# SCH_2023-10-16.net
KiCad netlist of a schematic drawn in EasyEDA
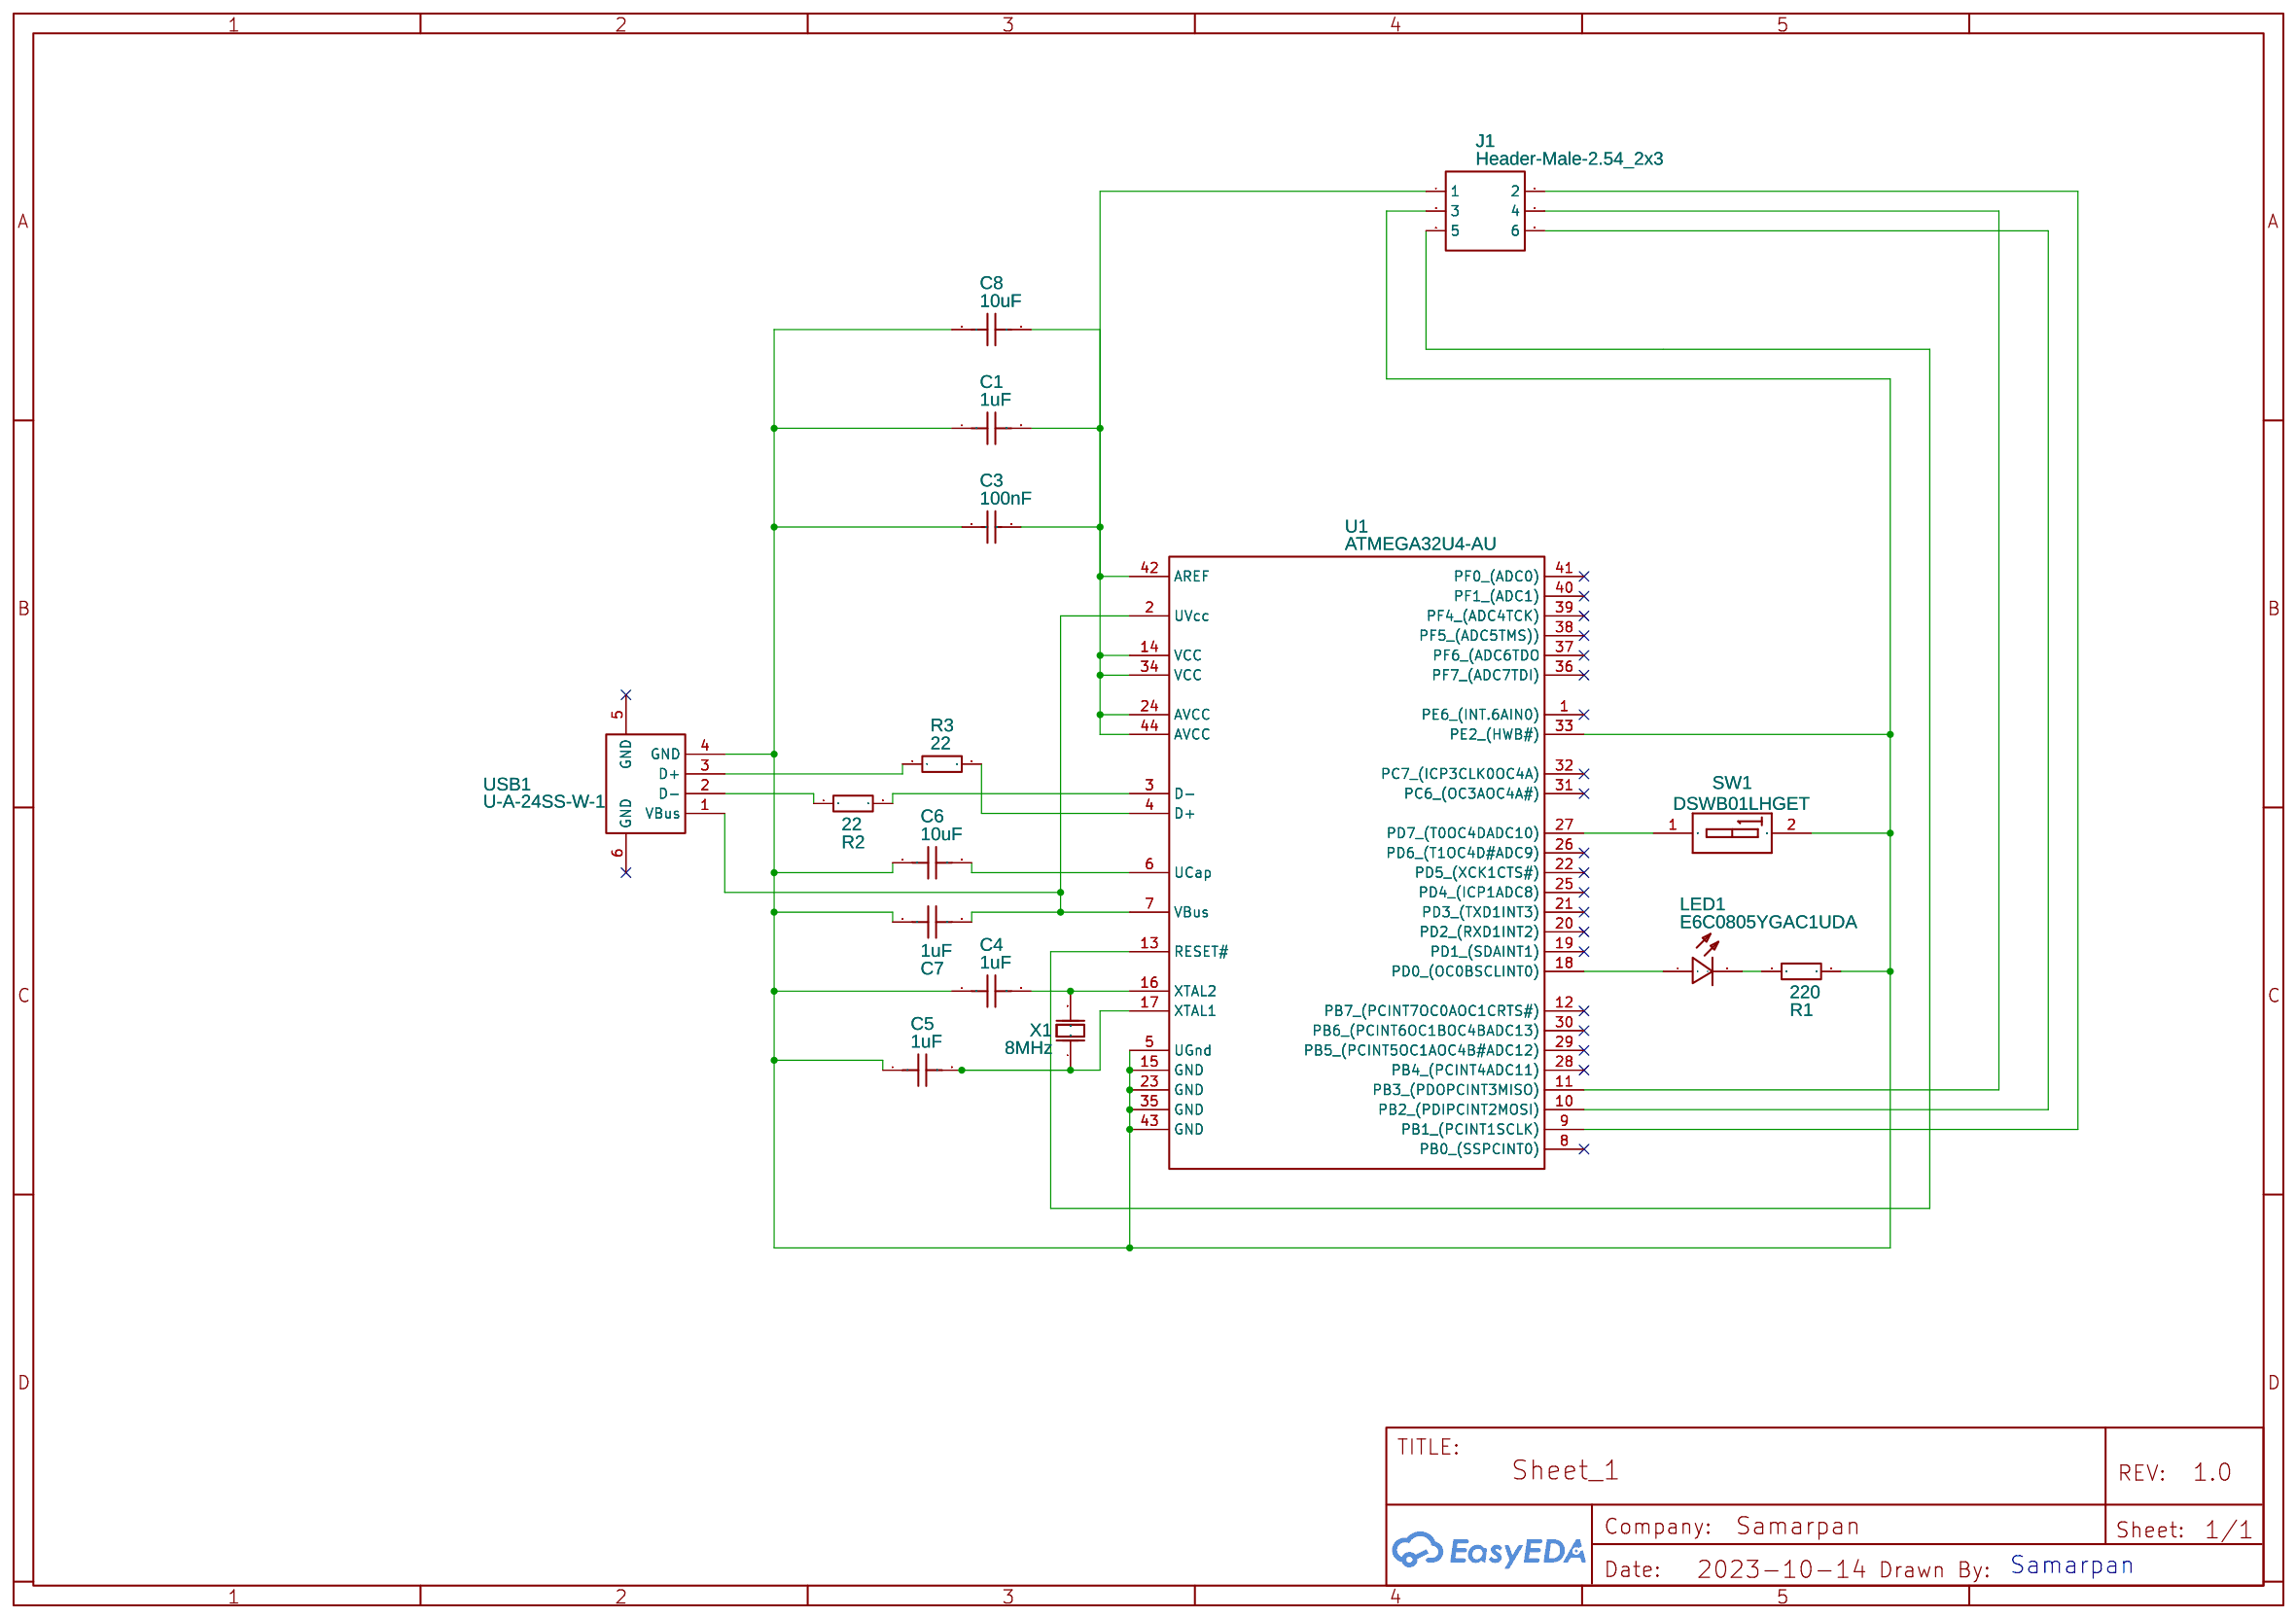
[diagram p0: schematic sheet]

(export (version "E")
  (design (tool "Eeschema 10.0.6"))
  (components
    (comp (ref "C1")
      (value "1uF")
      (fields (field (name "Manufacturer Part") "CC0402KRX5R6BB105") (field (name "Manufacturer") "YAGEO"))
      (libsource (lib "") (part "CC0402KRX5R6BB105"))
    )
    (comp (ref "C3")
      (value "100nF")
      (fields (field (name "Manufacturer Part") "0402B104K160NT") (field (name "Manufacturer") "FH"))
      (libsource (lib "") (part "0402B104K160NT"))
    )
    (comp (ref "C4")
      (value "1uF")
      (fields (field (name "Manufacturer Part") "CC0402KRX5R6BB105") (field (name "Manufacturer") "YAGEO"))
      (libsource (lib "") (part "CC0402KRX5R6BB105"))
    )
    (comp (ref "C5")
      (value "1uF")
      (fields (field (name "Manufacturer Part") "CC0402KRX5R6BB105") (field (name "Manufacturer") "YAGEO"))
      (libsource (lib "") (part "CC0402KRX5R6BB105"))
    )
    (comp (ref "C6")
      (value "10uF")
      (fields (field (name "Manufacturer Part") "CL10A106KP8NNNC") (field (name "Manufacturer") "SAMSUNG"))
      (libsource (lib "") (part "CL10A106KP8NNNC"))
    )
    (comp (ref "C7")
      (value "1uF")
      (fields (field (name "Manufacturer Part") "CC0402KRX5R6BB105") (field (name "Manufacturer") "YAGEO"))
      (libsource (lib "") (part "CC0402KRX5R6BB105_1"))
    )
    (comp (ref "C8")
      (value "10uF")
      (fields (field (name "Manufacturer Part") "CL10A106KP8NNNC") (field (name "Manufacturer") "SAMSUNG"))
      (libsource (lib "") (part "CL10A106KP8NNNC"))
    )
    (comp (ref "J1")
      (value "Header-Male-2.54_2x3")
      (fields (field (name "Manufacturer") "BOOMELE"))
      (libsource (lib "") (part "Unknown_745_100"))
    )
    (comp (ref "LED1")
      (value "E6C0805YGAC1UDA")
      (fields (field (name "Manufacturer") "EKINGLUX"))
      (libsource (lib "") (part "Unknown_855_485"))
    )
    (comp (ref "R1")
      (value "220")
      (fields (field (name "Manufacturer Part") "ARG05FTC2200") (field (name "Manufacturer") "Viking Tech"))
      (libsource (lib "") (part "ARG05FTC2200"))
    )
    (comp (ref "R2")
      (value "22")
      (fields (field (name "Manufacturer Part") "TC0525F220JT5E") (field (name "Manufacturer") "UniOhm"))
      (libsource (lib "") (part "TC0525F220JT5E"))
    )
    (comp (ref "R3")
      (value "22")
      (fields (field (name "Manufacturer Part") "TC0525F220JT5E") (field (name "Manufacturer") "UniOhm"))
      (libsource (lib "") (part "TC0525F220JT5E"))
    )
    (comp (ref "SW1")
      (value "DSWB01LHGET")
      (fields (field (name "Manufacturer") "KE"))
      (libsource (lib "") (part "Unknown_870_415"))
    )
    (comp (ref "U1")
      (value "ATMEGA32U4-AU")
      (fields (field (name "Manufacturer") "MICROCHIP"))
      (libsource (lib "") (part "Unknown_680_435"))
    )
    (comp (ref "USB1")
      (value "U-A-24SS-W-1")
      (fields (field (name "Manufacturer") "Korean Hroparts Elec"))
      (libsource (lib "") (part "Unknown_330_395"))
    )
    (comp (ref "X1")
      (value "8MHz")
      (fields
        (field (name "Manufacturer Part") "XSHEELNANF-8MHZ")
        (field (name "Manufacturer") "TAITIEN Elec")
      )
      (libsource (lib "") (part "XSHEELNANF-8MHZ"))
    )
  )
  (nets
    (net (code "1") (name "Net-(LED1-+)") (class "Default")
      (node (ref "LED1") (pin "1") (pinfunction "+_1") (pintype "unspecified"))
      (node (ref "U1") (pin "18") (pinfunction "PD0_(OC0BSCLINT0)_18") (pintype "bidirectional"))
    )
    (net (code "2") (name "Net-(LED1--)") (class "Default")
      (node (ref "LED1") (pin "2") (pinfunction "-_2") (pintype "unspecified"))
      (node (ref "R1") (pin "1") (pinfunction "1_1") (pintype "unspecified"))
    )
    (net (code "3") (name "Net-(SW1-A1)") (class "Default")
      (node (ref "SW1") (pin "1") (pinfunction "A1_1") (pintype "input"))
      (node (ref "U1") (pin "27") (pinfunction "PD7_(T0OC4DADC10)_27") (pintype "bidirectional"))
    )
    (net (code "4") (name "Net-(U1-AREF)") (class "Default")
      (node (ref "C1") (pin "2") (pinfunction "2_2") (pintype "unspecified"))
      (node (ref "C3") (pin "2") (pinfunction "2_2") (pintype "input"))
      (node (ref "C8") (pin "2") (pinfunction "2_2") (pintype "unspecified"))
      (node (ref "J1") (pin "1") (pinfunction "1_1") (pintype "input"))
      (node (ref "U1") (pin "14") (pinfunction "VCC_14") (pintype "passive"))
      (node (ref "U1") (pin "24") (pinfunction "AVCC_24") (pintype "passive"))
      (node (ref "U1") (pin "34") (pinfunction "VCC_34") (pintype "passive"))
      (node (ref "U1") (pin "42") (pinfunction "AREF_42") (pintype "unspecified"))
      (node (ref "U1") (pin "44") (pinfunction "AVCC_44") (pintype "passive"))
    )
    (net (code "5") (name "Net-(U1-D+)") (class "Default")
      (node (ref "R3") (pin "2") (pinfunction "2_2") (pintype "input"))
      (node (ref "U1") (pin "4") (pinfunction "D+_4") (pintype "bidirectional"))
    )
    (net (code "6") (name "Net-(U1-D-)") (class "Default")
      (node (ref "R2") (pin "2") (pinfunction "2_2") (pintype "input"))
      (node (ref "U1") (pin "3") (pinfunction "D-_3") (pintype "bidirectional"))
    )
    (net (code "7") (name "Net-(U1-PB1_(PCINT1SCLK))") (class "Default")
      (node (ref "J1") (pin "2") (pinfunction "2_2") (pintype "input"))
      (node (ref "U1") (pin "9") (pinfunction "PB1_(PCINT1SCLK)_9") (pintype "bidirectional"))
    )
    (net (code "8") (name "Net-(U1-PB2_(PDIPCINT2MOSI))") (class "Default")
      (node (ref "J1") (pin "6") (pinfunction "6_6") (pintype "input"))
      (node (ref "U1") (pin "10") (pinfunction "PB2_(PDIPCINT2MOSI)_10") (pintype "bidirectional"))
    )
    (net (code "9") (name "Net-(U1-PB3_(PDOPCINT3MISO))") (class "Default")
      (node (ref "J1") (pin "4") (pinfunction "4_4") (pintype "input"))
      (node (ref "U1") (pin "11") (pinfunction "PB3_(PDOPCINT3MISO)_11") (pintype "bidirectional"))
    )
    (net (code "10") (name "Net-(U1-PE2_(HWB#))") (class "Default")
      (node (ref "C1") (pin "1") (pinfunction "1_1") (pintype "unspecified"))
      (node (ref "C3") (pin "1") (pinfunction "1_1") (pintype "input"))
      (node (ref "C4") (pin "1") (pinfunction "1_1") (pintype "unspecified"))
      (node (ref "C5") (pin "1") (pinfunction "1_1") (pintype "unspecified"))
      (node (ref "C6") (pin "1") (pinfunction "1_1") (pintype "unspecified"))
      (node (ref "C7") (pin "1") (pinfunction "1_1") (pintype "unspecified"))
      (node (ref "C8") (pin "1") (pinfunction "1_1") (pintype "unspecified"))
      (node (ref "J1") (pin "3") (pinfunction "3_3") (pintype "input"))
      (node (ref "R1") (pin "2") (pinfunction "2_2") (pintype "unspecified"))
      (node (ref "SW1") (pin "2") (pinfunction "2_2") (pintype "input"))
      (node (ref "U1") (pin "15") (pinfunction "GND_15") (pintype "passive"))
      (node (ref "U1") (pin "23") (pinfunction "GND_23") (pintype "passive"))
      (node (ref "U1") (pin "33") (pinfunction "PE2_(HWB#)_33") (pintype "bidirectional"))
      (node (ref "U1") (pin "35") (pinfunction "GND_35") (pintype "passive"))
      (node (ref "U1") (pin "43") (pinfunction "GND_43") (pintype "passive"))
      (node (ref "U1") (pin "5") (pinfunction "UGnd_5") (pintype "passive"))
      (node (ref "USB1") (pin "4") (pinfunction "GND_4") (pintype "unspecified"))
    )
    (net (code "11") (name "Net-(U1-RESET#)") (class "Default")
      (node (ref "J1") (pin "5") (pinfunction "5_5") (pintype "input"))
      (node (ref "U1") (pin "13") (pinfunction "RESET#_13") (pintype "unspecified"))
    )
    (net (code "12") (name "Net-(U1-UCap)") (class "Default")
      (node (ref "C6") (pin "2") (pinfunction "2_2") (pintype "unspecified"))
      (node (ref "U1") (pin "6") (pinfunction "UCap_6") (pintype "unspecified"))
    )
    (net (code "13") (name "Net-(U1-UVcc)") (class "Default")
      (node (ref "C7") (pin "2") (pinfunction "2_2") (pintype "unspecified"))
      (node (ref "U1") (pin "2") (pinfunction "UVcc_2") (pintype "passive"))
      (node (ref "U1") (pin "7") (pinfunction "VBus_7") (pintype "unspecified"))
      (node (ref "USB1") (pin "1") (pinfunction "VBus_1") (pintype "unspecified"))
    )
    (net (code "14") (name "Net-(U1-XTAL1)") (class "Default")
      (node (ref "C5") (pin "2") (pinfunction "2_2") (pintype "unspecified"))
      (node (ref "U1") (pin "17") (pinfunction "XTAL1_17") (pintype "unspecified"))
      (node (ref "X1") (pin "1") (pinfunction "OSC1_1") (pintype "input"))
    )
    (net (code "15") (name "Net-(U1-XTAL2)") (class "Default")
      (node (ref "C4") (pin "2") (pinfunction "2_2") (pintype "unspecified"))
      (node (ref "U1") (pin "16") (pinfunction "XTAL2_16") (pintype "output"))
      (node (ref "X1") (pin "2") (pinfunction "OSC2_2") (pintype "input"))
    )
    (net (code "16") (name "Net-(USB1-D+)") (class "Default")
      (node (ref "R3") (pin "1") (pinfunction "1_1") (pintype "input"))
      (node (ref "USB1") (pin "3") (pinfunction "D+_3") (pintype "unspecified"))
    )
    (net (code "17") (name "Net-(USB1-D-)") (class "Default")
      (node (ref "R2") (pin "1") (pinfunction "1_1") (pintype "input"))
      (node (ref "USB1") (pin "2") (pinfunction "D-_2") (pintype "unspecified"))
    )
    (net (code "18") (name "unconnected-(U1-PB0_(SSPCINT0)-Pad8)") (class "Default")
      (node (ref "U1") (pin "8") (pinfunction "PB0_(SSPCINT0)_8") (pintype "bidirectional+no_connect"))
    )
    (net (code "19") (name "unconnected-(U1-PB4_(PCINT4ADC11)-Pad28)") (class "Default")
      (node (ref "U1") (pin "28") (pinfunction "PB4_(PCINT4ADC11)_28") (pintype "bidirectional+no_connect"))
    )
    (net (code "20") (name "unconnected-(U1-PB5_(PCINT5OC1AOC4B#ADC12)-Pad29)") (class "Default")
      (node (ref "U1") (pin "29") (pinfunction "PB5_(PCINT5OC1AOC4B#ADC12)_29") (pintype "bidirectional+no_connect"))
    )
    (net (code "21") (name "unconnected-(U1-PB6_(PCINT6OC1BOC4BADC13)-Pad30)") (class "Default")
      (node (ref "U1") (pin "30") (pinfunction "PB6_(PCINT6OC1BOC4BADC13)_30") (pintype "bidirectional+no_connect"))
    )
    (net (code "22") (name "unconnected-(U1-PB7_(PCINT7OC0AOC1CRTS#)-Pad12)") (class "Default")
      (node (ref "U1") (pin "12") (pinfunction "PB7_(PCINT7OC0AOC1CRTS#)_12") (pintype "bidirectional+no_connect"))
    )
    (net (code "23") (name "unconnected-(U1-PC6_(OC3AOC4A#)-Pad31)") (class "Default")
      (node (ref "U1") (pin "31") (pinfunction "PC6_(OC3AOC4A#)_31") (pintype "bidirectional+no_connect"))
    )
    (net (code "24") (name "unconnected-(U1-PC7_(ICP3CLK0OC4A)-Pad32)") (class "Default")
      (node (ref "U1") (pin "32") (pinfunction "PC7_(ICP3CLK0OC4A)_32") (pintype "bidirectional+no_connect"))
    )
    (net (code "25") (name "unconnected-(U1-PD1_(SDAINT1)-Pad19)") (class "Default")
      (node (ref "U1") (pin "19") (pinfunction "PD1_(SDAINT1)_19") (pintype "bidirectional+no_connect"))
    )
    (net (code "26") (name "unconnected-(U1-PD2_(RXD1INT2)-Pad20)") (class "Default")
      (node (ref "U1") (pin "20") (pinfunction "PD2_(RXD1INT2)_20") (pintype "bidirectional+no_connect"))
    )
    (net (code "27") (name "unconnected-(U1-PD3_(TXD1INT3)-Pad21)") (class "Default")
      (node (ref "U1") (pin "21") (pinfunction "PD3_(TXD1INT3)_21") (pintype "bidirectional+no_connect"))
    )
    (net (code "28") (name "unconnected-(U1-PD4_(ICP1ADC8)-Pad25)") (class "Default")
      (node (ref "U1") (pin "25") (pinfunction "PD4_(ICP1ADC8)_25") (pintype "bidirectional+no_connect"))
    )
    (net (code "29") (name "unconnected-(U1-PD5_(XCK1CTS#)-Pad22)") (class "Default")
      (node (ref "U1") (pin "22") (pinfunction "PD5_(XCK1CTS#)_22") (pintype "bidirectional+no_connect"))
    )
    (net (code "30") (name "unconnected-(U1-PD6_(T1OC4D#ADC9)-Pad26)") (class "Default")
      (node (ref "U1") (pin "26") (pinfunction "PD6_(T1OC4D#ADC9)_26") (pintype "bidirectional+no_connect"))
    )
    (net (code "31") (name "unconnected-(U1-PE6_(INT.6AIN0)-Pad1)") (class "Default")
      (node (ref "U1") (pin "1") (pinfunction "PE6_(INT.6AIN0)_1") (pintype "bidirectional+no_connect"))
    )
    (net (code "32") (name "unconnected-(U1-PF0_(ADC0)-Pad41)") (class "Default")
      (node (ref "U1") (pin "41") (pinfunction "PF0_(ADC0)_41") (pintype "bidirectional+no_connect"))
    )
    (net (code "33") (name "unconnected-(U1-PF1_(ADC1)-Pad40)") (class "Default")
      (node (ref "U1") (pin "40") (pinfunction "PF1_(ADC1)_40") (pintype "bidirectional+no_connect"))
    )
    (net (code "34") (name "unconnected-(U1-PF4_(ADC4TCK)-Pad39)") (class "Default")
      (node (ref "U1") (pin "39") (pinfunction "PF4_(ADC4TCK)_39") (pintype "bidirectional+no_connect"))
    )
    (net (code "35") (name "unconnected-(U1-PF5_(ADC5TMS))-Pad38)") (class "Default")
      (node (ref "U1") (pin "38") (pinfunction "PF5_(ADC5TMS))_38") (pintype "bidirectional+no_connect"))
    )
    (net (code "36") (name "unconnected-(U1-PF6_(ADC6TDO-Pad37)") (class "Default")
      (node (ref "U1") (pin "37") (pinfunction "PF6_(ADC6TDO_37") (pintype "bidirectional+no_connect"))
    )
    (net (code "37") (name "unconnected-(U1-PF7_(ADC7TDI)-Pad36)") (class "Default")
      (node (ref "U1") (pin "36") (pinfunction "PF7_(ADC7TDI)_36") (pintype "bidirectional+no_connect"))
    )
    (net (code "38") (name "unconnected-(USB1-GND-Pad5)") (class "Default")
      (node (ref "USB1") (pin "5") (pinfunction "GND_5") (pintype "unspecified+no_connect"))
    )
    (net (code "39") (name "unconnected-(USB1-GND-Pad6)") (class "Default")
      (node (ref "USB1") (pin "6") (pinfunction "GND_6") (pintype "unspecified+no_connect"))
    )
  )
)
